# Main.net
KiCad netlist of a schematic drawn in Altium Designer
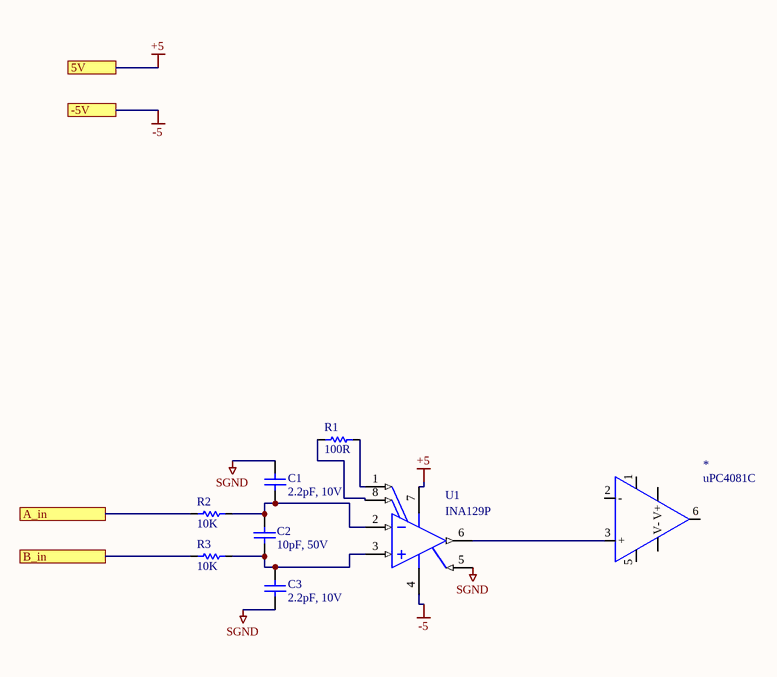
[diagram p0: Main.SchDoc]

(export (version "E")
  (design (tool "Eeschema 10.0.6"))
  (components
    (comp (ref "*")
      (value "uPC4081C")
      (description "Operational Amplifier, 1 Func, 20000uV Offset-Max, BIPolar, PDIP8")
      (libsource (lib "Revolve NTNU") (part "uPC4081C-Symbol-1"))
    )
    (comp (ref "C1")
      (value "2.2pF, 10V")
      (footprint "0402 capacitor, IPC Medium Density")
      (description "2.2uF, 10V, 10%, X7R, 0402")
      (libsource (lib "Revolve NTNU") (part "CAP"))
    )
    (comp (ref "C2")
      (value "10pF, 50V")
      (footprint "0402 capacitor, IPC Medium Density")
      (description "12pF, 50V, 2%, NP0, 0402")
      (libsource (lib "Revolve NTNU") (part "CAP"))
    )
    (comp (ref "C3")
      (value "2.2pF, 10V")
      (footprint "0402 capacitor, IPC Medium Density")
      (description "2.2uF, 10V, 10%, X7R, 0402")
      (libsource (lib "Revolve NTNU") (part "CAP"))
    )
    (comp (ref "R1")
      (value "100R")
      (footprint "RESC1005X04M")
      (description "100R, 1%, 1/16W, 0402")
      (libsource (lib "Revolve NTNU") (part "Resistor"))
    )
    (comp (ref "R2")
      (value "10K")
      (footprint "RESC1005X04N")
      (description "10K, 1%, 1/16W, 0402")
      (libsource (lib "Revolve NTNU") (part "Resistor"))
    )
    (comp (ref "R3")
      (value "10K")
      (footprint "RESC1005X04N")
      (description "10K, 1%, 1/16W, 0402")
      (libsource (lib "Revolve NTNU") (part "Resistor"))
    )
    (comp (ref "U1")
      (value "INA129P")
      (footprint "P0008A")
      (fields (field (name "MANUFACTURER") "Texas Instruments"))
      (libsource (lib "Components - 06.03.23 - 21.50") (part "CMP-0992-00137-2"))
    )
  )
  (nets
    (net (code "1") (name "+5") (class "Default")
      (node (ref "U1") (pin "7") (pinfunction "V+_7") (pintype "power_in"))
    )
    (net (code "2") (name "-5") (class "Default")
      (node (ref "U1") (pin "4") (pinfunction "V-_4") (pintype "power_in"))
    )
    (net (code "3") (name "/A_in") (class "Default")
      (node (ref "R2") (pin "1") (pinfunction "1_1") (pintype "passive"))
    )
    (net (code "4") (name "/B_in") (class "Default")
      (node (ref "R3") (pin "1") (pinfunction "1_1") (pintype "passive"))
    )
    (net (code "5") (name "Net-(*-+)") (class "Default")
      (node (ref "*") (pin "3") (pinfunction "+_3") (pintype "passive"))
      (node (ref "U1") (pin "6") (pinfunction "VO_6") (pintype "output"))
    )
    (net (code "6") (name "Net-(R1-Pad1)") (class "Default")
      (node (ref "R1") (pin "1") (pinfunction "1_1") (pintype "passive"))
      (node (ref "U1") (pin "8") (pinfunction "RG_8") (pintype "input"))
    )
    (net (code "7") (name "Net-(R1-Pad2)") (class "Default")
      (node (ref "R1") (pin "2") (pinfunction "2_2") (pintype "passive"))
      (node (ref "U1") (pin "1") (pinfunction "RG_1") (pintype "input"))
    )
    (net (code "8") (name "Net-(U1-VIN+)") (class "Default")
      (node (ref "C2") (pin "2") (pinfunction "2_2") (pintype "passive"))
      (node (ref "C3") (pin "2") (pinfunction "2_2") (pintype "passive"))
      (node (ref "R3") (pin "2") (pinfunction "2_2") (pintype "passive"))
      (node (ref "U1") (pin "3") (pinfunction "VIN+_3") (pintype "input"))
    )
    (net (code "9") (name "Net-(U1-VIN-)") (class "Default")
      (node (ref "C1") (pin "1") (pinfunction "1_1") (pintype "passive"))
      (node (ref "C2") (pin "1") (pinfunction "1_1") (pintype "passive"))
      (node (ref "R2") (pin "2") (pinfunction "2_2") (pintype "passive"))
      (node (ref "U1") (pin "2") (pinfunction "VIN-_2") (pintype "input"))
    )
    (net (code "10") (name "SGND") (class "Default")
      (node (ref "C1") (pin "2") (pinfunction "2_2") (pintype "passive"))
      (node (ref "C3") (pin "1") (pinfunction "1_1") (pintype "passive"))
      (node (ref "U1") (pin "5") (pinfunction "REF_5") (pintype "input"))
    )
    (net (code "11") (name "unconnected-(*---Pad2)") (class "Default")
      (node (ref "*") (pin "2") (pinfunction "-_2") (pintype "passive"))
    )
    (net (code "12") (name "unconnected-(*-O-Pad6)") (class "Default")
      (node (ref "*") (pin "6") (pinfunction "O_6") (pintype "passive"))
    )
    (net (code "13") (name "unconnected-(*-Offset-Pad5)") (class "Default")
      (node (ref "*") (pin "5") (pinfunction "Offset_5") (pintype "passive"))
    )
    (net (code "14") (name "unconnected-(*-V+-Pad7)") (class "Default")
      (node (ref "*") (pin "7") (pinfunction "V+_7") (pintype "passive"))
    )
    (net (code "15") (name "unconnected-(*-V--Pad4)") (class "Default")
      (node (ref "*") (pin "4") (pinfunction "V-_4") (pintype "passive"))
    )
    (net (code "16") (name "unconnected-(*-offset-Pad1)") (class "Default")
      (node (ref "*") (pin "1") (pinfunction "offset_1") (pintype "passive"))
    )
  )
)
